# CW308T_ADUCM3029.net
KiCad netlist of a schematic drawn in Altium Designer
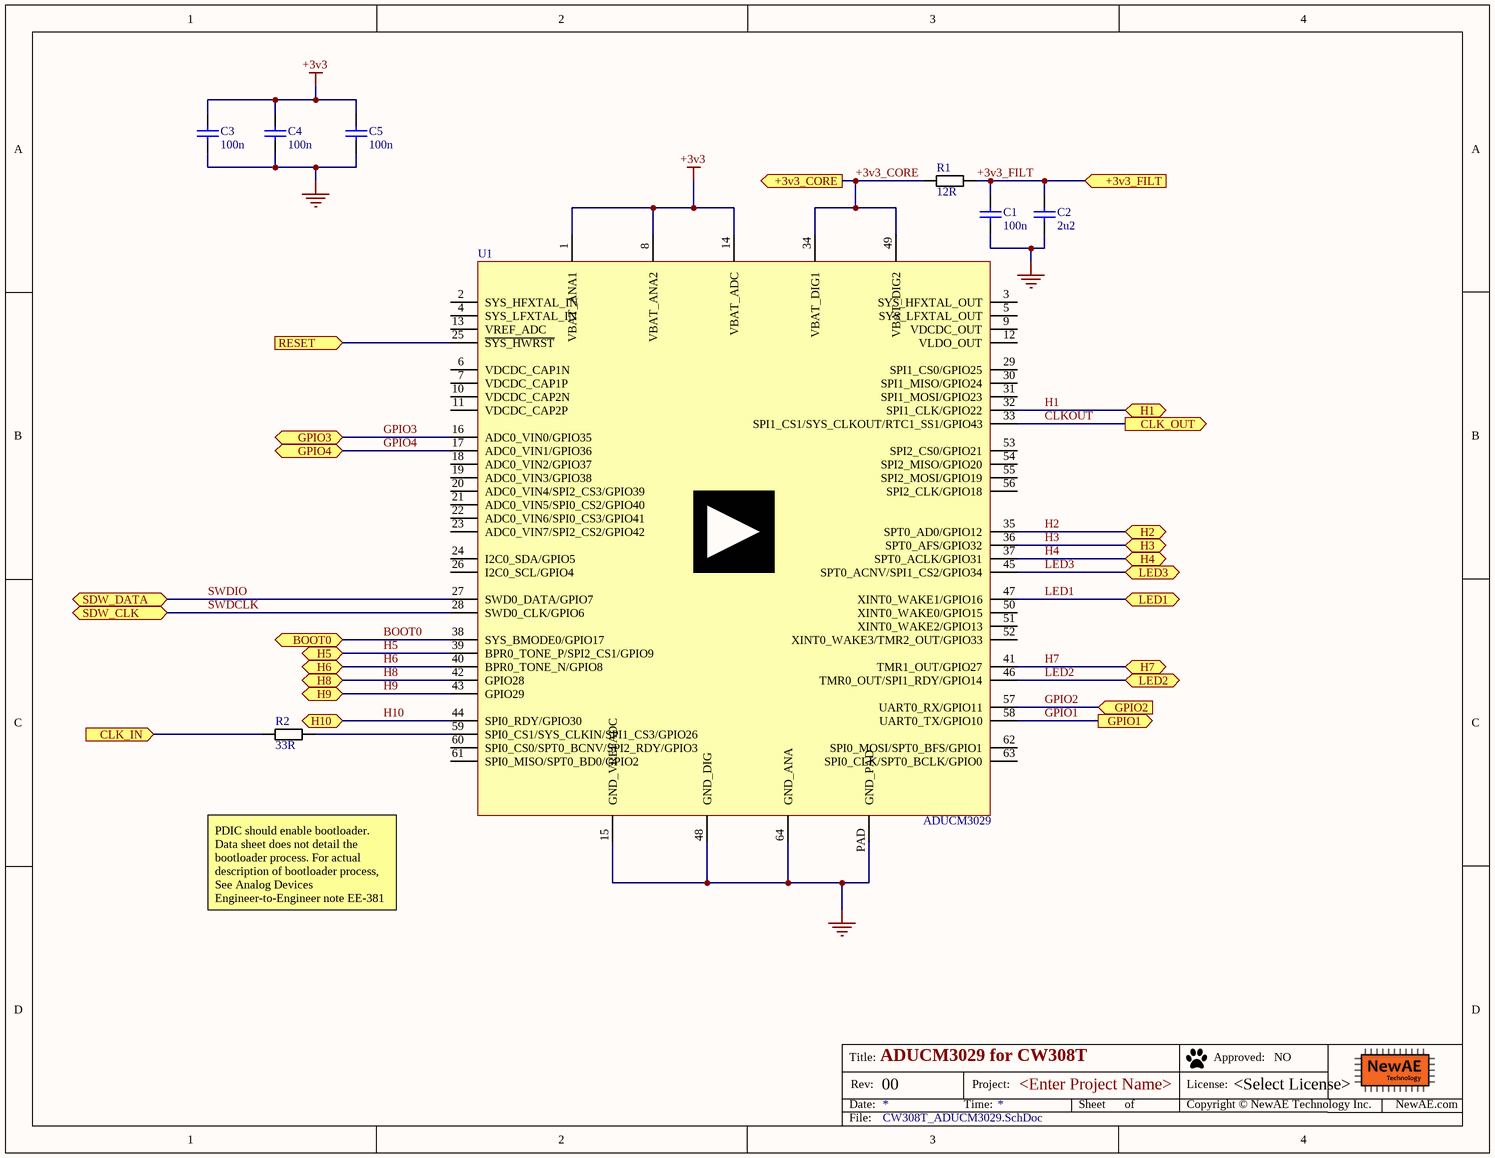
[diagram p0: CW308T_ADUCM3029.SchDoc]

(export (version "E")
  (design (tool "Eeschema 10.0.6"))
  (components
    (comp (ref "C1")
      (value "100n")
      (footprint "CAPC0603_M")
      (description "100n, 0603")
      (fields (field (name "PART NUMBER") "CCHIP-100n-0603"))
      (libsource (lib "NewAE_AltiumLib") (part "CAP"))
    )
    (comp (ref "C2")
      (value "2u2")
      (footprint "CAPC0603_M")
      (description "2u2, 0603")
      (fields (field (name "PART NUMBER") "CCHIP-2u2-0603"))
      (libsource (lib "NewAE_AltiumLib") (part "CAP"))
    )
    (comp (ref "C3")
      (value "100n")
      (footprint "CAPC0603_M")
      (description "100n, 0603")
      (fields (field (name "PART NUMBER") "CCHIP-100n-0603"))
      (libsource (lib "NewAE_AltiumLib") (part "CAP"))
    )
    (comp (ref "C4")
      (value "100n")
      (footprint "CAPC0603_M")
      (description "100n, 0603")
      (fields (field (name "PART NUMBER") "CCHIP-100n-0603"))
      (libsource (lib "NewAE_AltiumLib") (part "CAP"))
    )
    (comp (ref "C5")
      (value "100n")
      (footprint "CAPC0603_M")
      (description "100n, 0603")
      (fields (field (name "PART NUMBER") "CCHIP-100n-0603"))
      (libsource (lib "NewAE_AltiumLib") (part "CAP"))
    )
    (comp (ref "R1")
      (value "12R")
      (footprint "RESC1608X55N")
      (description "12R res, 0603, 1%, 1/10W")
      (fields (field (name "PART NUMBER") "RCHIP-12R-0603") (field (name "TOLERANCE") "1%"))
      (libsource (lib "NewAE_AltiumLib") (part "RES-EU"))
    )
    (comp (ref "R2")
      (value "33R")
      (footprint "RESC1608X55N")
      (description "33R res, 0603, 1%, 1/10W")
      (fields (field (name "PART NUMBER") "RCHIP-33R-0603") (field (name "TOLERANCE") "1%"))
      (libsource (lib "NewAE_AltiumLib") (part "RES-EU"))
    )
    (comp (ref "U1")
      (value "ADUCM3029")
      (footprint "LFCSP-64")
      (description "IC MCU 32BIT 256KB FLASH 64LFCSP")
      (fields (field (name "PART NUMBER") "ADUCM3029BCPZ"))
      (libsource (lib "NewAE_AltiumLib") (part "ADUCM3029"))
    )
  )
  (nets
    (net (code "1") (name "+3v3") (class "Default")
      (node (ref "C3") (pin "1") (pinfunction "1_1") (pintype "passive"))
      (node (ref "C4") (pin "1") (pinfunction "1_1") (pintype "passive"))
      (node (ref "C5") (pin "1") (pinfunction "1_1") (pintype "passive"))
      (node (ref "U1") (pin "1") (pinfunction "VBAT_ANA1_1") (pintype "passive"))
      (node (ref "U1") (pin "14") (pinfunction "VBAT_ADC_14") (pintype "passive"))
      (node (ref "U1") (pin "8") (pinfunction "VBAT_ANA2_8") (pintype "passive"))
    )
    (net (code "2") (name "/+3v3_CORE") (class "Default")
      (node (ref "R1") (pin "1") (pinfunction "1_1") (pintype "passive"))
      (node (ref "U1") (pin "34") (pinfunction "VBAT_DIG1_34") (pintype "passive"))
      (node (ref "U1") (pin "49") (pinfunction "VBAT_DIG2_49") (pintype "passive"))
    )
    (net (code "3") (name "/+3v3_FILT") (class "Default")
      (node (ref "C1") (pin "1") (pinfunction "1_1") (pintype "passive"))
      (node (ref "C2") (pin "1") (pinfunction "1_1") (pintype "passive"))
      (node (ref "R1") (pin "2") (pinfunction "2_2") (pintype "passive"))
    )
    (net (code "4") (name "/BOOT0") (class "Default")
      (node (ref "U1") (pin "38") (pinfunction "SYS_BMODE0/GPIO17_38") (pintype "passive"))
    )
    (net (code "5") (name "/CLKOUT") (class "Default")
      (node (ref "U1") (pin "33") (pinfunction "SPI1_CS1/SYS_CLKOUT/RTC1_SS1/GPIO43_33") (pintype "passive"))
    )
    (net (code "6") (name "/CLK_IN") (class "Default")
      (node (ref "R2") (pin "1") (pinfunction "1_1") (pintype "passive"))
    )
    (net (code "7") (name "/GPIO1") (class "Default")
      (node (ref "U1") (pin "58") (pinfunction "UART0_TX/GPIO10_58") (pintype "passive"))
    )
    (net (code "8") (name "/GPIO2") (class "Default")
      (node (ref "U1") (pin "57") (pinfunction "UART0_RX/GPIO11_57") (pintype "passive"))
    )
    (net (code "9") (name "/GPIO3") (class "Default")
      (node (ref "U1") (pin "16") (pinfunction "ADC0_VIN0/GPIO35_16") (pintype "passive"))
    )
    (net (code "10") (name "/GPIO4") (class "Default")
      (node (ref "U1") (pin "17") (pinfunction "ADC0_VIN1/GPIO36_17") (pintype "passive"))
    )
    (net (code "11") (name "/H1") (class "Default")
      (node (ref "U1") (pin "32") (pinfunction "SPI1_CLK/GPIO22_32") (pintype "passive"))
    )
    (net (code "12") (name "/H2") (class "Default")
      (node (ref "U1") (pin "35") (pinfunction "SPT0_AD0/GPIO12_35") (pintype "passive"))
    )
    (net (code "13") (name "/H3") (class "Default")
      (node (ref "U1") (pin "36") (pinfunction "SPT0_AFS/GPIO32_36") (pintype "passive"))
    )
    (net (code "14") (name "/H4") (class "Default")
      (node (ref "U1") (pin "37") (pinfunction "SPT0_ACLK/GPIO31_37") (pintype "passive"))
    )
    (net (code "15") (name "/H5") (class "Default")
      (node (ref "U1") (pin "39") (pinfunction "BPR0_TONE_P/SPI2_CS1/GPIO9_39") (pintype "passive"))
    )
    (net (code "16") (name "/H6") (class "Default")
      (node (ref "U1") (pin "40") (pinfunction "BPR0_TONE_N/GPIO8_40") (pintype "passive"))
    )
    (net (code "17") (name "/H7") (class "Default")
      (node (ref "U1") (pin "41") (pinfunction "TMR1_OUT/GPIO27_41") (pintype "passive"))
    )
    (net (code "18") (name "/H8") (class "Default")
      (node (ref "U1") (pin "42") (pinfunction "GPIO28_42") (pintype "passive"))
    )
    (net (code "19") (name "/H9") (class "Default")
      (node (ref "U1") (pin "43") (pinfunction "GPIO29_43") (pintype "passive"))
    )
    (net (code "20") (name "/H10") (class "Default")
      (node (ref "U1") (pin "44") (pinfunction "SPI0_RDY/GPIO30_44") (pintype "passive"))
    )
    (net (code "21") (name "/LED1") (class "Default")
      (node (ref "U1") (pin "47") (pinfunction "XINT0_WAKE1/GPIO16_47") (pintype "passive"))
    )
    (net (code "22") (name "/LED2") (class "Default")
      (node (ref "U1") (pin "46") (pinfunction "TMR0_OUT/SPI1_RDY/GPIO14_46") (pintype "passive"))
    )
    (net (code "23") (name "/LED3") (class "Default")
      (node (ref "U1") (pin "45") (pinfunction "SPT0_ACNV/SPI1_CS2/GPIO34_45") (pintype "passive"))
    )
    (net (code "24") (name "/RESET") (class "Default")
      (node (ref "U1") (pin "25") (pinfunction "~{SYS_HWRST}_25") (pintype "passive"))
    )
    (net (code "25") (name "/SWDCLK") (class "Default")
      (node (ref "U1") (pin "28") (pinfunction "SWD0_CLK/GPIO6_28") (pintype "passive"))
    )
    (net (code "26") (name "/SWDIO") (class "Default")
      (node (ref "U1") (pin "27") (pinfunction "SWD0_DATA/GPIO7_27") (pintype "passive"))
    )
    (net (code "27") (name "GND") (class "Default")
      (node (ref "C1") (pin "2") (pinfunction "2_2") (pintype "passive"))
      (node (ref "C2") (pin "2") (pinfunction "2_2") (pintype "passive"))
      (node (ref "C3") (pin "2") (pinfunction "2_2") (pintype "passive"))
      (node (ref "C4") (pin "2") (pinfunction "2_2") (pintype "passive"))
      (node (ref "C5") (pin "2") (pinfunction "2_2") (pintype "passive"))
      (node (ref "U1") (pin "15") (pinfunction "GND_VREFADC_15") (pintype "passive"))
      (node (ref "U1") (pin "48") (pinfunction "GND_DIG_48") (pintype "passive"))
      (node (ref "U1") (pin "64") (pinfunction "GND_ANA_64") (pintype "passive"))
      (node (ref "U1") (pin "PAD") (pinfunction "GND_PAD_PAD") (pintype "passive"))
    )
    (net (code "28") (name "Net-(U1-SPI0_CS1{slash}SYS_CLKIN{slash}SPI1_CS3{slash}GPIO26)") (class "Default")
      (node (ref "R2") (pin "2") (pinfunction "2_2") (pintype "passive"))
      (node (ref "U1") (pin "59") (pinfunction "SPI0_CS1/SYS_CLKIN/SPI1_CS3/GPIO26_59") (pintype "passive"))
    )
    (net (code "29") (name "unconnected-(U1-ADC0_VIN2{slash}GPIO37-Pad18)") (class "Default")
      (node (ref "U1") (pin "18") (pinfunction "ADC0_VIN2/GPIO37_18") (pintype "passive"))
    )
    (net (code "30") (name "unconnected-(U1-ADC0_VIN3{slash}GPIO38-Pad19)") (class "Default")
      (node (ref "U1") (pin "19") (pinfunction "ADC0_VIN3/GPIO38_19") (pintype "passive"))
    )
    (net (code "31") (name "unconnected-(U1-ADC0_VIN4{slash}SPI2_CS3{slash}GPIO39-Pad20)") (class "Default")
      (node (ref "U1") (pin "20") (pinfunction "ADC0_VIN4/SPI2_CS3/GPIO39_20") (pintype "passive"))
    )
    (net (code "32") (name "unconnected-(U1-ADC0_VIN5{slash}SPI0_CS2{slash}GPIO40-Pad21)") (class "Default")
      (node (ref "U1") (pin "21") (pinfunction "ADC0_VIN5/SPI0_CS2/GPIO40_21") (pintype "passive"))
    )
    (net (code "33") (name "unconnected-(U1-ADC0_VIN6{slash}SPI0_CS3{slash}GPIO41-Pad22)") (class "Default")
      (node (ref "U1") (pin "22") (pinfunction "ADC0_VIN6/SPI0_CS3/GPIO41_22") (pintype "passive"))
    )
    (net (code "34") (name "unconnected-(U1-ADC0_VIN7{slash}SPI2_CS2{slash}GPIO42-Pad23)") (class "Default")
      (node (ref "U1") (pin "23") (pinfunction "ADC0_VIN7/SPI2_CS2/GPIO42_23") (pintype "passive"))
    )
    (net (code "35") (name "unconnected-(U1-I2C0_SCL{slash}GPIO4-Pad26)") (class "Default")
      (node (ref "U1") (pin "26") (pinfunction "I2C0_SCL/GPIO4_26") (pintype "passive"))
    )
    (net (code "36") (name "unconnected-(U1-I2C0_SDA{slash}GPIO5-Pad24)") (class "Default")
      (node (ref "U1") (pin "24") (pinfunction "I2C0_SDA/GPIO5_24") (pintype "passive"))
    )
    (net (code "37") (name "unconnected-(U1-SPI0_CLK{slash}SPT0_BCLK{slash}GPIO0-Pad63)") (class "Default")
      (node (ref "U1") (pin "63") (pinfunction "SPI0_CLK/SPT0_BCLK/GPIO0_63") (pintype "passive"))
    )
    (net (code "38") (name "unconnected-(U1-SPI0_CS0{slash}SPT0_BCNV{slash}SPI2_RDY{slash}GPIO3-Pad60)") (class "Default")
      (node (ref "U1") (pin "60") (pinfunction "SPI0_CS0/SPT0_BCNV/SPI2_RDY/GPIO3_60") (pintype "passive"))
    )
    (net (code "39") (name "unconnected-(U1-SPI0_MISO{slash}SPT0_BD0{slash}GPIO2-Pad61)") (class "Default")
      (node (ref "U1") (pin "61") (pinfunction "SPI0_MISO/SPT0_BD0/GPIO2_61") (pintype "passive"))
    )
    (net (code "40") (name "unconnected-(U1-SPI0_MOSI{slash}SPT0_BFS{slash}GPIO1-Pad62)") (class "Default")
      (node (ref "U1") (pin "62") (pinfunction "SPI0_MOSI/SPT0_BFS/GPIO1_62") (pintype "passive"))
    )
    (net (code "41") (name "unconnected-(U1-SPI1_CS0{slash}GPIO25-Pad29)") (class "Default")
      (node (ref "U1") (pin "29") (pinfunction "SPI1_CS0/GPIO25_29") (pintype "passive"))
    )
    (net (code "42") (name "unconnected-(U1-SPI1_MISO{slash}GPIO24-Pad30)") (class "Default")
      (node (ref "U1") (pin "30") (pinfunction "SPI1_MISO/GPIO24_30") (pintype "passive"))
    )
    (net (code "43") (name "unconnected-(U1-SPI1_MOSI{slash}GPIO23-Pad31)") (class "Default")
      (node (ref "U1") (pin "31") (pinfunction "SPI1_MOSI/GPIO23_31") (pintype "passive"))
    )
    (net (code "44") (name "unconnected-(U1-SPI2_CLK{slash}GPIO18-Pad56)") (class "Default")
      (node (ref "U1") (pin "56") (pinfunction "SPI2_CLK/GPIO18_56") (pintype "passive"))
    )
    (net (code "45") (name "unconnected-(U1-SPI2_CS0{slash}GPIO21-Pad53)") (class "Default")
      (node (ref "U1") (pin "53") (pinfunction "SPI2_CS0/GPIO21_53") (pintype "passive"))
    )
    (net (code "46") (name "unconnected-(U1-SPI2_MISO{slash}GPIO20-Pad54)") (class "Default")
      (node (ref "U1") (pin "54") (pinfunction "SPI2_MISO/GPIO20_54") (pintype "passive"))
    )
    (net (code "47") (name "unconnected-(U1-SPI2_MOSI{slash}GPIO19-Pad55)") (class "Default")
      (node (ref "U1") (pin "55") (pinfunction "SPI2_MOSI/GPIO19_55") (pintype "passive"))
    )
    (net (code "48") (name "unconnected-(U1-SYS_HFXTAL_IN-Pad2)") (class "Default")
      (node (ref "U1") (pin "2") (pinfunction "SYS_HFXTAL_IN_2") (pintype "passive"))
    )
    (net (code "49") (name "unconnected-(U1-SYS_HFXTAL_OUT-Pad3)") (class "Default")
      (node (ref "U1") (pin "3") (pinfunction "SYS_HFXTAL_OUT_3") (pintype "passive"))
    )
    (net (code "50") (name "unconnected-(U1-SYS_LFXTAL_IN-Pad4)") (class "Default")
      (node (ref "U1") (pin "4") (pinfunction "SYS_LFXTAL_IN_4") (pintype "passive"))
    )
    (net (code "51") (name "unconnected-(U1-SYS_LFXTAL_OUT-Pad5)") (class "Default")
      (node (ref "U1") (pin "5") (pinfunction "SYS_LFXTAL_OUT_5") (pintype "passive"))
    )
    (net (code "52") (name "unconnected-(U1-VDCDC_CAP1N-Pad6)") (class "Default")
      (node (ref "U1") (pin "6") (pinfunction "VDCDC_CAP1N_6") (pintype "passive"))
    )
    (net (code "53") (name "unconnected-(U1-VDCDC_CAP1P-Pad7)") (class "Default")
      (node (ref "U1") (pin "7") (pinfunction "VDCDC_CAP1P_7") (pintype "passive"))
    )
    (net (code "54") (name "unconnected-(U1-VDCDC_CAP2N-Pad10)") (class "Default")
      (node (ref "U1") (pin "10") (pinfunction "VDCDC_CAP2N_10") (pintype "passive"))
    )
    (net (code "55") (name "unconnected-(U1-VDCDC_CAP2P-Pad11)") (class "Default")
      (node (ref "U1") (pin "11") (pinfunction "VDCDC_CAP2P_11") (pintype "passive"))
    )
    (net (code "56") (name "unconnected-(U1-VDCDC_OUT-Pad9)") (class "Default")
      (node (ref "U1") (pin "9") (pinfunction "VDCDC_OUT_9") (pintype "passive"))
    )
    (net (code "57") (name "unconnected-(U1-VLDO_OUT-Pad12)") (class "Default")
      (node (ref "U1") (pin "12") (pinfunction "VLDO_OUT_12") (pintype "passive"))
    )
    (net (code "58") (name "unconnected-(U1-VREF_ADC-Pad13)") (class "Default")
      (node (ref "U1") (pin "13") (pinfunction "VREF_ADC_13") (pintype "passive"))
    )
    (net (code "59") (name "unconnected-(U1-XINT0_WAKE0{slash}GPIO15-Pad50)") (class "Default")
      (node (ref "U1") (pin "50") (pinfunction "XINT0_WAKE0/GPIO15_50") (pintype "passive"))
    )
    (net (code "60") (name "unconnected-(U1-XINT0_WAKE2{slash}GPIO13-Pad51)") (class "Default")
      (node (ref "U1") (pin "51") (pinfunction "XINT0_WAKE2/GPIO13_51") (pintype "passive"))
    )
    (net (code "61") (name "unconnected-(U1-XINT0_WAKE3{slash}TMR2_OUT{slash}GPIO33-Pad52)") (class "Default")
      (node (ref "U1") (pin "52") (pinfunction "XINT0_WAKE3/TMR2_OUT/GPIO33_52") (pintype "passive"))
    )
  )
)
